# LCDPlug.net
KiCad netlist of a schematic drawn in EAGLE
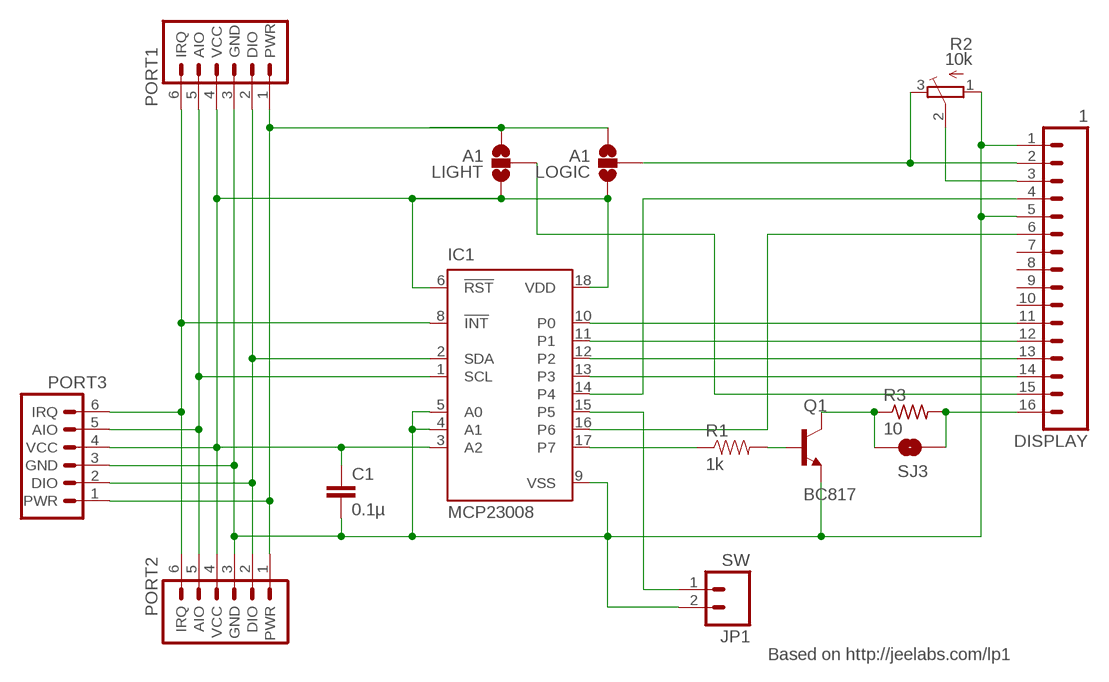
[diagram p0: schematic, sheet 1]

(export (version "E")
  (design (tool "Eeschema 10.0.6"))
  (components
    (comp (ref "C1")
      (value "0.1µ")
      (footprint "eagle-import:0603-CAP")
      (libsource (lib "eagle-import") (part "CAP0603-CAP"))
    )
    (comp (ref "DISPLAY")
      (value "1")
      (footprint "eagle-import:1X16")
      (libsource (lib "eagle-import") (part "M16PTH"))
    )
    (comp (ref "IC1")
      (value "MCP23008")
      (footprint "eagle-import:SO18W")
      (libsource (lib "eagle-import") (part "MCP23008T"))
    )
    (comp (ref "JP1")
      (value "SW")
      (footprint "eagle-import:1X02")
      (libsource (lib "eagle-import") (part "M02PTH"))
    )
    (comp (ref "LIGHT")
      (value "A1")
      (footprint "eagle-import:SJ_2")
      (libsource (lib "eagle-import") (part "SOLDERJUMPER_2WAYT"))
    )
    (comp (ref "LOGIC")
      (value "A1")
      (footprint "eagle-import:SJ_2")
      (libsource (lib "eagle-import") (part "SOLDERJUMPER_2WAYT"))
    )
    (comp (ref "PORT1")
      (value "JEEPORT")
      (footprint "eagle-import:PORT6PIN")
      (libsource (lib "eagle-import") (part "JEEPORT-LONGPADS"))
    )
    (comp (ref "PORT2")
      (value "JEEPORT")
      (footprint "eagle-import:PORT6PIN")
      (libsource (lib "eagle-import") (part "JEEPORT-LONGPADS"))
    )
    (comp (ref "PORT3")
      (value "JEEPORT")
      (footprint "eagle-import:PORT6PIN")
      (libsource (lib "eagle-import") (part "JEEPORT-LONGPADS"))
    )
    (comp (ref "Q1")
      (value "BC817")
      (footprint "eagle-import:SOT23-3")
      (libsource (lib "eagle-import") (part "TRANSISTOR_NPNSOT23-3"))
    )
    (comp (ref "R1")
      (value "1k")
      (footprint "eagle-import:0603-RES")
      (libsource (lib "eagle-import") (part "RESISTOR0603-RES"))
    )
    (comp (ref "R2")
      (value "10k")
      (footprint "eagle-import:SM-42_43W")
      (libsource (lib "eagle-import") (part "TRIM_EU-SM-42/43W"))
    )
    (comp (ref "R3")
      (value "10")
      (footprint "eagle-import:0204_7")
      (libsource (lib "eagle-import") (part "R-US_0204/7"))
    )
    (comp (ref "SJ3")
      (value "SOLDERJUMPERNO")
      (footprint "eagle-import:SJ_2S-NO")
      (libsource (lib "eagle-import") (part "SOLDERJUMPERNO"))
    )
  )
  (nets
    (net (code "1") (name "Net-(DISPLAY-Pad15)") (class "Default")
      (node (ref "DISPLAY") (pin "15") (pinfunction "15_15") (pintype "passive"))
      (node (ref "LIGHT") (pin "2") (pinfunction "2_2") (pintype "passive"))
    )
    (net (code "2") (name "Net-(DISPLAY-Pad16)") (class "Default")
      (node (ref "DISPLAY") (pin "16") (pinfunction "16_16") (pintype "passive"))
      (node (ref "R3") (pin "2") (pinfunction "2_2") (pintype "passive"))
      (node (ref "SJ3") (pin "1") (pinfunction "1_1") (pintype "passive"))
    )
    (net (code "3") (name "Net-(IC1-A0)") (class "Default")
      (node (ref "C1") (pin "2") (pinfunction "2_2") (pintype "passive"))
      (node (ref "DISPLAY") (pin "1") (pinfunction "1_1") (pintype "passive"))
      (node (ref "DISPLAY") (pin "5") (pinfunction "5_5") (pintype "passive"))
      (node (ref "IC1") (pin "4") (pinfunction "A1_4") (pintype "input"))
      (node (ref "IC1") (pin "5") (pinfunction "A0_5") (pintype "input"))
      (node (ref "IC1") (pin "9") (pinfunction "VSS_9") (pintype "power_in"))
      (node (ref "JP1") (pin "2") (pinfunction "2_2") (pintype "passive"))
      (node (ref "PORT1") (pin "3") (pinfunction "GND_3") (pintype "power_in"))
      (node (ref "PORT2") (pin "3") (pinfunction "GND_3") (pintype "power_in"))
      (node (ref "PORT3") (pin "3") (pinfunction "GND_3") (pintype "power_in"))
      (node (ref "Q1") (pin "2") (pinfunction "E_2") (pintype "passive"))
      (node (ref "R2") (pin "1") (pinfunction "A_1") (pintype "passive"))
    )
    (net (code "4") (name "Net-(IC1-A2)") (class "Default")
      (node (ref "C1") (pin "1") (pinfunction "1_1") (pintype "passive"))
      (node (ref "IC1") (pin "18") (pinfunction "VDD_18") (pintype "power_in"))
      (node (ref "IC1") (pin "3") (pinfunction "A2_3") (pintype "input"))
      (node (ref "IC1") (pin "6") (pinfunction "~{RST}_6") (pintype "input"))
      (node (ref "LIGHT") (pin "1") (pinfunction "1_1") (pintype "passive"))
      (node (ref "LOGIC") (pin "1") (pinfunction "1_1") (pintype "passive"))
      (node (ref "PORT1") (pin "4") (pinfunction "VCC_4") (pintype "power_in"))
      (node (ref "PORT2") (pin "4") (pinfunction "VCC_4") (pintype "power_in"))
      (node (ref "PORT3") (pin "4") (pinfunction "VCC_4") (pintype "power_in"))
    )
    (net (code "5") (name "Net-(IC1-P0)") (class "Default")
      (node (ref "DISPLAY") (pin "11") (pinfunction "11_11") (pintype "passive"))
      (node (ref "IC1") (pin "10") (pinfunction "P0_10") (pintype "bidirectional"))
    )
    (net (code "6") (name "Net-(IC1-P1)") (class "Default")
      (node (ref "DISPLAY") (pin "12") (pinfunction "12_12") (pintype "passive"))
      (node (ref "IC1") (pin "11") (pinfunction "P1_11") (pintype "bidirectional"))
    )
    (net (code "7") (name "Net-(IC1-P2)") (class "Default")
      (node (ref "DISPLAY") (pin "13") (pinfunction "13_13") (pintype "passive"))
      (node (ref "IC1") (pin "12") (pinfunction "P2_12") (pintype "bidirectional"))
    )
    (net (code "8") (name "Net-(IC1-P3)") (class "Default")
      (node (ref "DISPLAY") (pin "14") (pinfunction "14_14") (pintype "passive"))
      (node (ref "IC1") (pin "13") (pinfunction "P3_13") (pintype "bidirectional"))
    )
    (net (code "9") (name "Net-(IC1-P4)") (class "Default")
      (node (ref "DISPLAY") (pin "4") (pinfunction "4_4") (pintype "passive"))
      (node (ref "IC1") (pin "14") (pinfunction "P4_14") (pintype "bidirectional"))
    )
    (net (code "10") (name "Net-(IC1-P5)") (class "Default")
      (node (ref "IC1") (pin "15") (pinfunction "P5_15") (pintype "bidirectional"))
      (node (ref "JP1") (pin "1") (pinfunction "1_1") (pintype "passive"))
    )
    (net (code "11") (name "Net-(IC1-P6)") (class "Default")
      (node (ref "DISPLAY") (pin "6") (pinfunction "6_6") (pintype "passive"))
      (node (ref "IC1") (pin "16") (pinfunction "P6_16") (pintype "bidirectional"))
    )
    (net (code "12") (name "Net-(IC1-P7)") (class "Default")
      (node (ref "IC1") (pin "17") (pinfunction "P7_17") (pintype "bidirectional"))
      (node (ref "R1") (pin "1") (pinfunction "1_1") (pintype "passive"))
    )
    (net (code "13") (name "Net-(IC1-SCL)") (class "Default")
      (node (ref "IC1") (pin "1") (pinfunction "SCL_1") (pintype "input"))
      (node (ref "PORT1") (pin "5") (pinfunction "AIO_5") (pintype "bidirectional"))
      (node (ref "PORT2") (pin "5") (pinfunction "AIO_5") (pintype "bidirectional"))
      (node (ref "PORT3") (pin "5") (pinfunction "AIO_5") (pintype "bidirectional"))
    )
    (net (code "14") (name "Net-(IC1-SDA)") (class "Default")
      (node (ref "IC1") (pin "2") (pinfunction "SDA_2") (pintype "bidirectional"))
      (node (ref "PORT1") (pin "2") (pinfunction "DIO_2") (pintype "bidirectional"))
      (node (ref "PORT2") (pin "2") (pinfunction "DIO_2") (pintype "bidirectional"))
      (node (ref "PORT3") (pin "2") (pinfunction "DIO_2") (pintype "bidirectional"))
    )
    (net (code "15") (name "Net-(IC1-~{INT})") (class "Default")
      (node (ref "IC1") (pin "8") (pinfunction "~{INT}_8") (pintype "output"))
      (node (ref "PORT1") (pin "6") (pinfunction "IRQ_6") (pintype "bidirectional"))
      (node (ref "PORT2") (pin "6") (pinfunction "IRQ_6") (pintype "bidirectional"))
      (node (ref "PORT3") (pin "6") (pinfunction "IRQ_6") (pintype "bidirectional"))
    )
    (net (code "16") (name "Net-(PORT1-PWR)") (class "Default")
      (node (ref "LIGHT") (pin "3") (pinfunction "3_3") (pintype "passive"))
      (node (ref "LOGIC") (pin "3") (pinfunction "3_3") (pintype "passive"))
      (node (ref "PORT1") (pin "1") (pinfunction "PWR_1") (pintype "power_in"))
      (node (ref "PORT2") (pin "1") (pinfunction "PWR_1") (pintype "power_in"))
      (node (ref "PORT3") (pin "1") (pinfunction "PWR_1") (pintype "power_in"))
    )
    (net (code "17") (name "Net-(Q1-B)") (class "Default")
      (node (ref "Q1") (pin "1") (pinfunction "B_1") (pintype "passive"))
      (node (ref "R1") (pin "2") (pinfunction "2_2") (pintype "passive"))
    )
    (net (code "18") (name "Net-(Q1-C)") (class "Default")
      (node (ref "Q1") (pin "3") (pinfunction "C_3") (pintype "passive"))
      (node (ref "R3") (pin "1") (pinfunction "1_1") (pintype "passive"))
      (node (ref "SJ3") (pin "2") (pinfunction "2_2") (pintype "passive"))
    )
    (net (code "19") (name "Net-(R2-E)") (class "Default")
      (node (ref "DISPLAY") (pin "2") (pinfunction "2_2") (pintype "passive"))
      (node (ref "LOGIC") (pin "2") (pinfunction "2_2") (pintype "passive"))
      (node (ref "R2") (pin "3") (pinfunction "E_3") (pintype "passive"))
    )
    (net (code "20") (name "Net-(R2-S)") (class "Default")
      (node (ref "DISPLAY") (pin "3") (pinfunction "3_3") (pintype "passive"))
      (node (ref "R2") (pin "2") (pinfunction "S_2") (pintype "passive"))
    )
    (net (code "21") (name "unconnected-(DISPLAY-Pad7)") (class "Default")
      (node (ref "DISPLAY") (pin "7") (pinfunction "7_7") (pintype "passive"))
    )
    (net (code "22") (name "unconnected-(DISPLAY-Pad8)") (class "Default")
      (node (ref "DISPLAY") (pin "8") (pinfunction "8_8") (pintype "passive"))
    )
    (net (code "23") (name "unconnected-(DISPLAY-Pad9)") (class "Default")
      (node (ref "DISPLAY") (pin "9") (pinfunction "9_9") (pintype "passive"))
    )
    (net (code "24") (name "unconnected-(DISPLAY-Pad10)") (class "Default")
      (node (ref "DISPLAY") (pin "10") (pinfunction "10_10") (pintype "passive"))
    )
  )
)
